# Mainboard_Wifi_Interface.net
KiCad netlist of a schematic drawn in Altium Designer
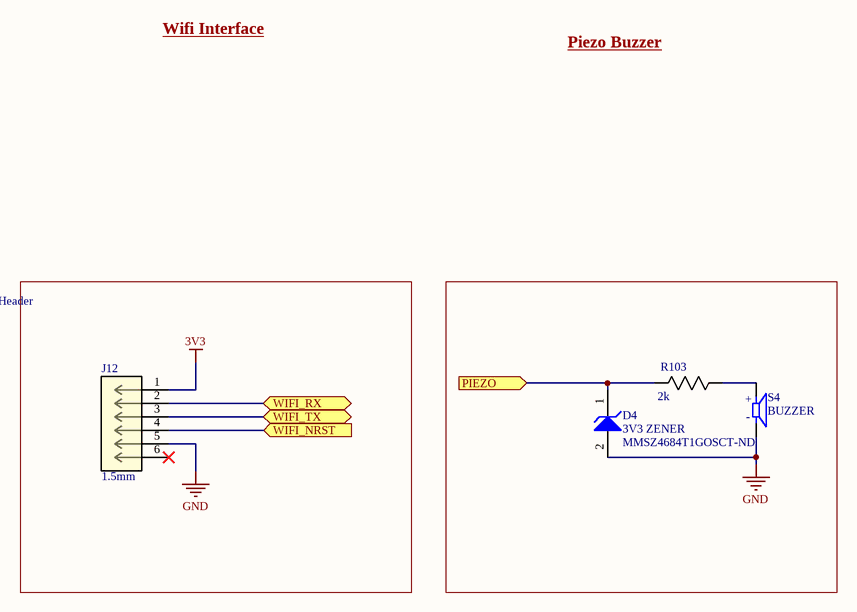
[diagram p0: Mainboard_Wifi_Interface.SchDoc]

(export (version "E")
  (design (tool "Eeschema 10.0.6"))
  (components
    (comp (ref "D4")
      (value "3V3 ZENER")
      (footprint "ONSC-SOD-123-2-425-04_V")
      (description "Zener 3V3 Voltage Regulator, 500 mW, 2-Pin SOD-123, Pb-Free, Tape and Reel")
      (fields
        (field (name "PARTNUMBER") "MMSZ4684T1G")
        (field (name "MANUFACTURER") "On Semiconductor")
        (field (name "SUPPLIER PART NUMBER 1") "MMSZ4684T1GOSCT-ND")
      )
      (libsource (lib "AltiumLibraries") (part "DIODE ZENER 3.3 500mW"))
    )
    (comp (ref "J12")
      (value "1.5mm")
      (footprint "6POS JST")
      (description "Conn Shrouded Header HDR 6 POS 1.5mm Solder RA Thru-Hole Box")
      (fields (field (name "MANUFACTURER") "JST") (field (name "MANUFACTURER PART NUMBER") "S6B-ZR(LF)(SN)"))
      (libsource (lib "AltiumLibraries") (part "CN 6POS JST RA"))
    )
    (comp (ref "R103")
      (value "2k")
      (footprint "0805")
      (description "RES SMD 2K OHM 5% 1/8W 0805")
      (fields (field (name "TOLERANCE") "5%"))
      (libsource (lib "AltiumLibraries") (part "RES 2k 1/8W"))
    )
    (comp (ref "S4")
      (value "BUZZER")
      (footprint "PKM13EPYH4000-A0")
      (libsource (lib "AltiumLibraries") (part "BUZZER PKM13EPYH4000-A0"))
    )
  )
  (nets
    (net (code "1") (name "/PIEZO") (class "Default")
      (node (ref "D4") (pin "1") (pinfunction "K_1") (pintype "passive"))
      (node (ref "R103") (pin "2") (pinfunction "R2_2") (pintype "passive"))
    )
    (net (code "2") (name "/WIFI_NRST") (class "Default")
      (node (ref "J12") (pin "4") (pinfunction "4_4") (pintype "passive"))
    )
    (net (code "3") (name "/WIFI_RX") (class "Default")
      (node (ref "J12") (pin "2") (pinfunction "2_2") (pintype "passive"))
    )
    (net (code "4") (name "/WIFI_TX") (class "Default")
      (node (ref "J12") (pin "3") (pinfunction "3_3") (pintype "passive"))
    )
    (net (code "5") (name "3V3") (class "Default")
      (node (ref "J12") (pin "1") (pinfunction "1_1") (pintype "passive"))
    )
    (net (code "6") (name "GND") (class "Default")
      (node (ref "D4") (pin "2") (pinfunction "A_2") (pintype "passive"))
      (node (ref "J12") (pin "5") (pinfunction "5_5") (pintype "passive"))
      (node (ref "S4") (pin "N") (pinfunction "N_N") (pintype "passive"))
    )
    (net (code "7") (name "Net-(R103-R1)") (class "Default")
      (node (ref "R103") (pin "1") (pinfunction "R1_1") (pintype "passive"))
      (node (ref "S4") (pin "P") (pinfunction "P_P") (pintype "passive"))
    )
    (net (code "8") (name "unconnected-(J12-Pad6)") (class "Default")
      (node (ref "J12") (pin "6") (pinfunction "6_6") (pintype "passive+no_connect"))
    )
  )
)
